# TINY24.net
KiCad netlist of a schematic drawn in Altium Designer
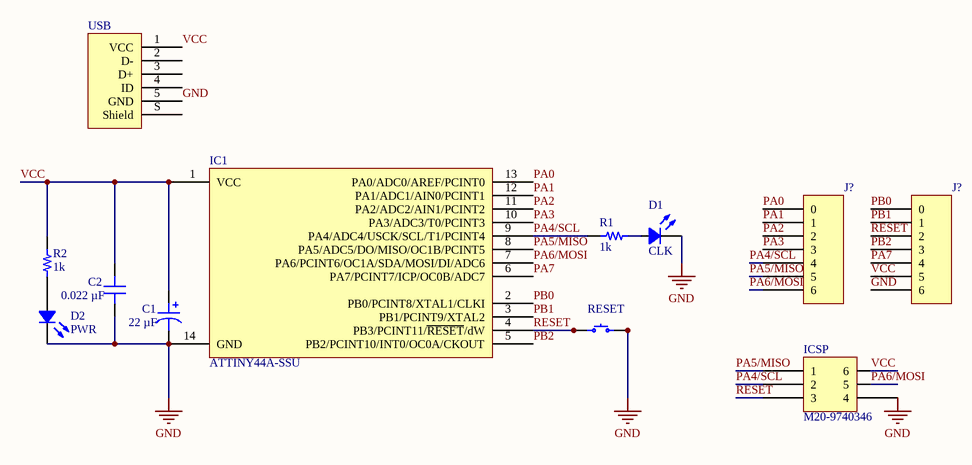
[diagram p0: TINY24.SchDoc]

(export (version "E")
  (design (tool "Eeschema 10.0.6"))
  (components
    (comp (ref "C1")
      (value "22 µF")
      (footprint "CAP POL 1206_3216")
      (description "293D105X9016A8T")
      (fields (field (name "MANUFACTURER") "Vishay Sprague") (field (name "TOLERANCE") "±10%"))
      (libsource (lib "Celestial Altium Library - altium_library") (part "Polarised Capacitor"))
    )
    (comp (ref "C2")
      (value "0.022 µF")
      (footprint "CAP 0402_1005")
      (description "CAP CER 0402 22NF 50V X7R 10%")
      (fields
        (field (name "PART NUMBER") "C0402C223K5RECAUTO")
        (field (name "CAPACITANCE") "0.022 µF")
        (field (name "MANUFACTURER") "KEMET")
      )
      (libsource (lib "Celestial Altium Library - altium_library") (part "Capacitor"))
    )
    (comp (ref "D1")
      (value "CLK")
      (footprint "LED 0805_2012 GREEN")
      (description "LED GREEN CLEAR 0805 SMD")
      (fields
        (field (name "PART NUMBER") "QTLP630C4TR")
        (field (name "MANUFACTURER") "Everlight Electronics Co Ltd")
      )
      (libsource (lib "Celestial Altium Library - altium_library") (part "LED"))
    )
    (comp (ref "D2")
      (value "PWR")
      (footprint "LED 0805_2012 GREEN")
      (description "LED GREEN CLEAR 0805 SMD")
      (fields
        (field (name "PART NUMBER") "QTLP630C4TR")
        (field (name "MANUFACTURER") "Everlight Electronics Co Ltd")
      )
      (libsource (lib "Celestial Altium Library - altium_library") (part "LED"))
    )
    (comp (ref "IC1")
      (value "ATTINY44A-SSU")
      (footprint "ATMEL SO-14 14S1")
      (description "IC MCU 8BIT 4KB FLASH 14SOIC")
      (fields (field (name "MANUFACTURER") "Microchip Technology"))
      (libsource (lib "Celestial Altium Library - altium_library") (part "Atmel ATtiny24A/44A/84A 14Pin"))
    )
    (comp (ref "ICSP")
      (value "M20-9740346")
      (footprint "HARWIN M20-9740345")
      (description "CONN HEADER R/A 6POS 2.54MM")
      (fields (field (name "MANUFACTURER") "Harwin Inc."))
      (libsource (lib "Celestial Altium Library - altium_library") (part "2X3 PIN DU"))
    )
    (comp (ref "J1")
      (value "7pin-2.54MaleHeader")
      (footprint "7Pin2.54Header")
      (description "2.54 Male Header DuPont 7pin")
      (libsource (lib "2.54 Headers Lib") (part "7pin-2.54MaleHeader"))
    )
    (comp (ref "J2")
      (value "7pin-2.54MaleHeader")
      (footprint "7Pin2.54Header")
      (description "2.54 Male Header DuPont 7pin")
      (libsource (lib "2.54 Headers Lib") (part "7pin-2.54MaleHeader"))
    )
    (comp (ref "R1")
      (value "1k")
      (footprint "RES 0402_1005")
      (description "RES 1K OHM 1% 1/5W 0402")
      (fields (field (name "PART NUMBER") "RCA04021K00FKEDHP") (field (name "MANUFACTURER") "Vishay Dale"))
      (libsource (lib "Celestial Altium Library - altium_library") (part "Resistor"))
    )
    (comp (ref "R2")
      (value "1k")
      (footprint "RES 0402_1005")
      (description "RES 1K OHM 1% 1/5W 0402")
      (fields (field (name "PART NUMBER") "RCA04021K00FKEDHP") (field (name "MANUFACTURER") "Vishay Dale"))
      (libsource (lib "Celestial Altium Library - altium_library") (part "Resistor"))
    )
    (comp (ref "RESET")
      (value "B3FS-1012P")
      (footprint "OMRON B3FS-1012P")
      (description "SWITCH TACTILE SPST-NO 0.05A 24V")
      (fields (field (name "MANUFACTURER") "Omron Electronics Inc-EMC Div"))
      (libsource (lib "Celestial Altium Library - altium_library") (part "SPST-NO 4 PIN"))
    )
    (comp (ref "USB")
      (value "10118193-0001LF")
      (footprint "FCI USB 10118193-0001LF")
      (description "CONN RCPT USB2.0 MICRO B SMD R/A")
      (fields (field (name "MANUFACTURER") "Amphenol ICC (FCI)"))
      (libsource (lib "Celestial Altium Library - altium_library") (part "USB 2.0 Type B Micro"))
    )
  )
  (nets
    (net (code "1") (name "/PA0") (class "Default")
      (node (ref "IC1") (pin "13") (pinfunction "PA0/ADC0/AREF/PCINT0_13") (pintype "passive"))
      (node (ref "J2") (pin "0") (pinfunction "0_0") (pintype "passive"))
    )
    (net (code "2") (name "/PA1") (class "Default")
      (node (ref "IC1") (pin "12") (pinfunction "PA1/ADC1/AIN0/PCINT1_12") (pintype "passive"))
      (node (ref "J2") (pin "1") (pinfunction "1_1") (pintype "passive"))
    )
    (net (code "3") (name "/PA2") (class "Default")
      (node (ref "IC1") (pin "11") (pinfunction "PA2/ADC2/AIN1/PCINT2_11") (pintype "passive"))
      (node (ref "J2") (pin "2") (pinfunction "2_2") (pintype "passive"))
    )
    (net (code "4") (name "/PA3") (class "Default")
      (node (ref "IC1") (pin "10") (pinfunction "PA3/ADC3/T0/PCINT3_10") (pintype "passive"))
      (node (ref "J2") (pin "3") (pinfunction "3_3") (pintype "passive"))
    )
    (net (code "5") (name "/PA4{slash}SCL") (class "Default")
      (node (ref "IC1") (pin "9") (pinfunction "PA4/ADC4/USCK/SCL/T1/PCINT4_9") (pintype "passive"))
      (node (ref "ICSP") (pin "2") (pinfunction "2_2") (pintype "passive"))
      (node (ref "J2") (pin "4") (pinfunction "4_4") (pintype "passive"))
      (node (ref "R1") (pin "1") (pinfunction "1_1") (pintype "passive"))
    )
    (net (code "6") (name "/PA5{slash}MISO") (class "Default")
      (node (ref "IC1") (pin "8") (pinfunction "PA5/ADC5/DO/MISO/OC1B/PCINT5_8") (pintype "passive"))
      (node (ref "ICSP") (pin "1") (pinfunction "1_1") (pintype "passive"))
      (node (ref "J2") (pin "5") (pinfunction "5_5") (pintype "passive"))
    )
    (net (code "7") (name "/PA6{slash}MOSI") (class "Default")
      (node (ref "IC1") (pin "7") (pinfunction "PA6/PCINT6/OC1A/SDA/MOSI/DI/ADC6_7") (pintype "passive"))
      (node (ref "ICSP") (pin "5") (pinfunction "5_5") (pintype "passive"))
      (node (ref "J2") (pin "6") (pinfunction "6_6") (pintype "passive"))
    )
    (net (code "8") (name "/PA7") (class "Default")
      (node (ref "IC1") (pin "6") (pinfunction "PA7/PCINT7/ICP/OC0B/ADC7_6") (pintype "passive"))
      (node (ref "J1") (pin "4") (pinfunction "4_4") (pintype "passive"))
    )
    (net (code "9") (name "/PB0") (class "Default")
      (node (ref "IC1") (pin "2") (pinfunction "PB0/PCINT8/XTAL1/CLKI_2") (pintype "passive"))
      (node (ref "J1") (pin "0") (pinfunction "0_0") (pintype "passive"))
    )
    (net (code "10") (name "/PB1") (class "Default")
      (node (ref "IC1") (pin "3") (pinfunction "PB1/PCINT9/XTAL2_3") (pintype "passive"))
      (node (ref "J1") (pin "1") (pinfunction "1_1") (pintype "passive"))
    )
    (net (code "11") (name "/PB2") (class "Default")
      (node (ref "IC1") (pin "5") (pinfunction "PB2/PCINT10/INT0/OC0A/CKOUT_5") (pintype "passive"))
      (node (ref "J1") (pin "3") (pinfunction "3_3") (pintype "passive"))
    )
    (net (code "12") (name "/RESET") (class "Default")
      (node (ref "IC1") (pin "4") (pinfunction "PB3/PCINT11/~{RESET}/dW_4") (pintype "passive"))
      (node (ref "ICSP") (pin "3") (pinfunction "3_3") (pintype "passive"))
      (node (ref "J1") (pin "2") (pinfunction "2_2") (pintype "passive"))
      (node (ref "RESET") (pin "1") (pinfunction "1_1") (pintype "passive"))
      (node (ref "RESET") (pin "2") (pinfunction "2_2") (pintype "passive"))
    )
    (net (code "13") (name "/VCC") (class "Default")
      (node (ref "C1") (pin "1") (pinfunction "1_1") (pintype "passive"))
      (node (ref "C2") (pin "2") (pinfunction "2_2") (pintype "passive"))
      (node (ref "IC1") (pin "1") (pinfunction "VCC_1") (pintype "passive"))
      (node (ref "ICSP") (pin "6") (pinfunction "6_6") (pintype "passive"))
      (node (ref "J1") (pin "5") (pinfunction "5_5") (pintype "passive"))
      (node (ref "R2") (pin "2") (pinfunction "2_2") (pintype "passive"))
      (node (ref "USB") (pin "1") (pinfunction "VCC_1") (pintype "passive"))
    )
    (net (code "14") (name "GND") (class "Default")
      (node (ref "C1") (pin "2") (pinfunction "2_2") (pintype "passive"))
      (node (ref "C2") (pin "1") (pinfunction "1_1") (pintype "passive"))
      (node (ref "D1") (pin "2") (pinfunction "2_2") (pintype "passive"))
      (node (ref "D2") (pin "2") (pinfunction "2_2") (pintype "passive"))
      (node (ref "IC1") (pin "14") (pinfunction "GND_14") (pintype "passive"))
      (node (ref "ICSP") (pin "4") (pinfunction "4_4") (pintype "passive"))
      (node (ref "J1") (pin "6") (pinfunction "6_6") (pintype "passive"))
      (node (ref "RESET") (pin "3") (pinfunction "3_3") (pintype "passive"))
      (node (ref "RESET") (pin "4") (pinfunction "4_4") (pintype "passive"))
      (node (ref "USB") (pin "5") (pinfunction "GND_5") (pintype "passive"))
    )
    (net (code "15") (name "Net-(D1-Pad1)") (class "Default")
      (node (ref "D1") (pin "1") (pinfunction "1_1") (pintype "passive"))
      (node (ref "R1") (pin "2") (pinfunction "2_2") (pintype "passive"))
    )
    (net (code "16") (name "Net-(D2-Pad1)") (class "Default")
      (node (ref "D2") (pin "1") (pinfunction "1_1") (pintype "passive"))
      (node (ref "R2") (pin "1") (pinfunction "1_1") (pintype "passive"))
    )
    (net (code "17") (name "unconnected-(USB-D+-Pad3)") (class "Default")
      (node (ref "USB") (pin "3") (pinfunction "D+_3") (pintype "passive"))
    )
    (net (code "18") (name "unconnected-(USB-D--Pad2)") (class "Default")
      (node (ref "USB") (pin "2") (pinfunction "D-_2") (pintype "passive"))
    )
    (net (code "19") (name "unconnected-(USB-ID-Pad4)") (class "Default")
      (node (ref "USB") (pin "4") (pinfunction "ID_4") (pintype "passive"))
    )
    (net (code "20") (name "unconnected-(USB-Shield-PadS)") (class "Default")
      (node (ref "USB") (pin "S") (pinfunction "Shield_S") (pintype "passive"))
    )
  )
)
